# LEDDimmer.net
KiCad netlist of a schematic drawn in Altium Designer
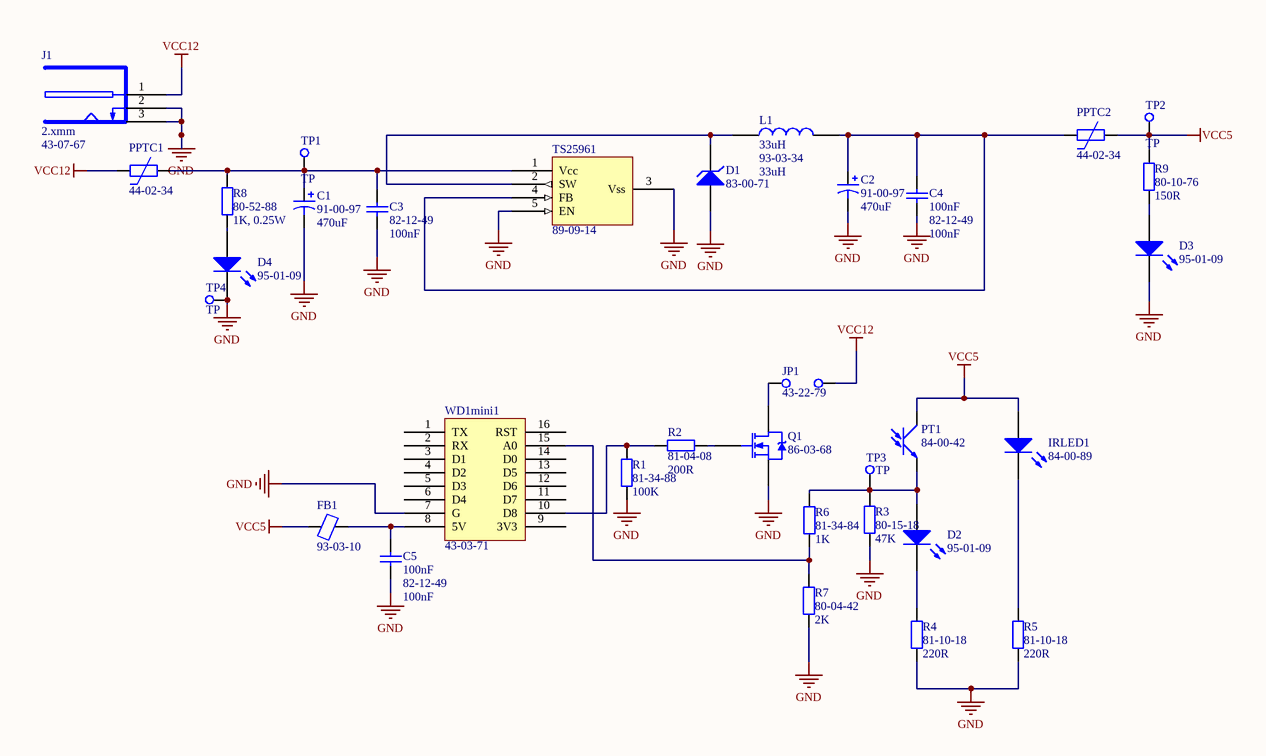
[diagram p0: LEDDimmer.SchDoc]

(export (version "E")
  (design (tool "Eeschema 10.0.6"))
  (components
    (comp (ref "C1")
      (value "470uF")
      (footprint "ELKO_CAP")
      (description "Polarized Capacitor")
      (fields (field (name "SUPPLIER") "91-00-97"))
      (libsource (lib "LEDDimmerLib") (part "CAP_ELECT"))
    )
    (comp (ref "C2")
      (value "470uF")
      (footprint "ELKO_CAP")
      (description "Polarized Capacitor")
      (fields (field (name "SUPPLIER") "91-00-97"))
      (libsource (lib "LEDDimmerLib") (part "CAP_ELECT"))
    )
    (comp (ref "C3")
      (value "100nF")
      (footprint "FP_0402_CAP_050")
      (description "Capacitor")
      (fields (field (name "SUPPLIER") "82-12-49"))
      (libsource (lib "LEDDimmerLib") (part "CAP_100n"))
    )
    (comp (ref "C4")
      (value "100nF")
      (footprint "FP_0402_CAP_050")
      (description "Capacitor")
      (fields (field (name "SUPPLIER") "82-12-49") (field (name "ALTIUM_VALUE") "100nF"))
      (libsource (lib "LEDDimmerLib") (part "CAP_100n"))
    )
    (comp (ref "C5")
      (value "100nF")
      (footprint "FP_0402_CAP_050")
      (description "Capacitor")
      (fields (field (name "SUPPLIER") "82-12-49") (field (name "ALTIUM_VALUE") "100nF"))
      (libsource (lib "LEDDimmerLib") (part "CAP_100n"))
    )
    (comp (ref "D1")
      (value "ZENER")
      (footprint "SCHOTTKY")
      (description "Zener Diode")
      (fields (field (name "SUPPLIER") "83-00-71"))
      (libsource (lib "LEDDimmerLib") (part "ZENER"))
    )
    (comp (ref "D2")
      (value "LED")
      (footprint "FP_0805_LED_GREEN")
      (description "Typical RED GaAs LED")
      (fields (field (name "SUPPLIER") "95-01-09"))
      (libsource (lib "LEDDimmerLib") (part "LED"))
    )
    (comp (ref "D3")
      (value "LED")
      (footprint "FP_0805_LED_RED")
      (description "Typical RED GaAs LED")
      (fields (field (name "SUPPLIER") "95-01-09"))
      (libsource (lib "LEDDimmerLib") (part "LED"))
    )
    (comp (ref "D4")
      (value "LED")
      (footprint "FP_0805_LED_RED")
      (description "Typical RED GaAs LED")
      (fields (field (name "SUPPLIER") "95-01-09"))
      (libsource (lib "LEDDimmerLib") (part "LED"))
    )
    (comp (ref "FB1")
      (value "FB")
      (footprint "FB")
      (description "Ferrite bead")
      (fields (field (name "SUPPLIER") "93-03-10"))
      (libsource (lib "LEDDimmerLib") (part "FB"))
    )
    (comp (ref "IRLED1")
      (value "IRLED")
      (footprint "IRLED")
      (description "InfraLED")
      (fields (field (name "SUPPLIER") "84-00-89"))
      (libsource (lib "LEDDimmerLib") (part "IRLED"))
    )
    (comp (ref "J1")
      (value "2.xmm")
      (footprint "FP_DC_TAP_ANYA")
      (description "2.xmm DC HEBA25 TÁPFESZÜLTSÉG ALJZAT ZÁRT, NYÁKBA 90°")
      (fields (field (name "SUPPLIER") "43-07-67"))
      (libsource (lib "LEDDimmerLib") (part "DC_TAP_ANYA"))
    )
    (comp (ref "JP1")
      (value "JUMPER")
      (footprint "CONN2")
      (description "Jumper Wire")
      (fields (field (name "SUPPLIER") "43-22-79"))
      (libsource (lib "LEDDimmerLib") (part "JUMPER"))
    )
    (comp (ref "L1")
      (value "33uH")
      (footprint "IND")
      (description "Inductor")
      (fields (field (name "SUPPLIER") "93-03-34") (field (name "ALTIUM_VALUE") "33uH"))
      (libsource (lib "LEDDimmerLib") (part "IND"))
    )
    (comp (ref "PPTC1")
      (value "PPTC")
      (footprint "PPTC")
      (description "Polymeric Positive Temperature Coefficient")
      (fields (field (name "SUPPLIER") "44-02-34"))
      (libsource (lib "LEDDimmerLib") (part "PPTC"))
    )
    (comp (ref "PPTC2")
      (value "PPTC")
      (footprint "PPTC")
      (description "Polymeric Positive Temperature Coefficient")
      (fields (field (name "SUPPLIER") "44-02-34"))
      (libsource (lib "LEDDimmerLib") (part "PPTC"))
    )
    (comp (ref "PT1")
      (value "PT")
      (footprint "IRLED")
      (description "Phototransistor")
      (fields (field (name "SUPPLIER") "84-00-42"))
      (libsource (lib "LEDDimmerLib") (part "PTRANS"))
    )
    (comp (ref "Q1")
      (value "NMOS")
      (footprint "IRL540N")
      (description "NXP - BSP030,115 - MOSFET, N CH, 30V, 10A, SOT223")
      (fields (field (name "SUPPLIER") "86-03-68"))
      (libsource (lib "LEDDimmerLib") (part "NMOS"))
    )
    (comp (ref "R1")
      (value "100K")
      (footprint "FP_0603_RES")
      (description "Resistor")
      (fields (field (name "SUPPLIER") "81-34-88"))
      (libsource (lib "LEDDimmerLib") (part "RES_100K"))
    )
    (comp (ref "R2")
      (value "200R")
      (footprint "FP_0603_RES")
      (description "Resistor")
      (fields (field (name "SUPPLIER") "81-04-08") (field (name "Comment") "200"))
      (libsource (lib "LEDDimmerLib") (part "RES_200R"))
    )
    (comp (ref "R3")
      (value "47K")
      (footprint "FP_0603_RES")
      (description "Resistor")
      (fields (field (name "SUPPLIER") "80-15-18"))
      (libsource (lib "LEDDimmerLib") (part "RES_47K"))
    )
    (comp (ref "R4")
      (value "220R")
      (footprint "FP_0603_RES")
      (description "Resistor")
      (fields (field (name "SUPPLIER") "81-10-18") (field (name "Comment") "220"))
      (libsource (lib "LEDDimmerLib") (part "RES_220R"))
    )
    (comp (ref "R5")
      (value "220R")
      (footprint "FP_0603_RES")
      (description "Resistor")
      (fields (field (name "SUPPLIER") "81-10-18") (field (name "Comment") "220"))
      (libsource (lib "LEDDimmerLib") (part "RES_220R"))
    )
    (comp (ref "R6")
      (value "1K")
      (footprint "FP_0603_RES")
      (description "Resistor")
      (fields (field (name "SUPPLIER") "81-34-84"))
      (libsource (lib "LEDDimmerLib") (part "RES_1K"))
    )
    (comp (ref "R7")
      (value "2K")
      (footprint "FP_0603_RES")
      (description "Resistor")
      (fields (field (name "SUPPLIER") "80-04-42"))
      (libsource (lib "LEDDimmerLib") (part "RES_2K"))
    )
    (comp (ref "R8")
      (value "1K, 0.25W")
      (footprint "FP_1206_RES")
      (description "Resistor")
      (fields (field (name "SUPPLIER") "80-52-88"))
      (libsource (lib "LEDDimmerLib") (part "RES_1K_025W"))
    )
    (comp (ref "R9")
      (value "150R")
      (footprint "FP_0805_RES")
      (description "Resistor")
      (fields (field (name "SUPPLIER") "80-10-76"))
      (libsource (lib "LEDDimmerLib") (part "RES_150R"))
    )
    (comp (ref "TP1")
      (value "TP")
      (footprint "FP_CONN1_TUSKE_254MM")
      (description "Test Point")
      (libsource (lib "LEDDimmerLib") (part "TP"))
    )
    (comp (ref "TP2")
      (value "TP")
      (footprint "FP_CONN1_TUSKE_254MM")
      (description "Test Point")
      (libsource (lib "LEDDimmerLib") (part "TP"))
    )
    (comp (ref "TP3")
      (value "TP")
      (footprint "FP_CONN1_TUSKE_254MM")
      (description "Test Point")
      (libsource (lib "LEDDimmerLib") (part "TP"))
    )
    (comp (ref "TP4")
      (value "TP")
      (footprint "FP_CONN1_TUSKE_254MM")
      (description "Test Point")
      (libsource (lib "LEDDimmerLib") (part "TP"))
    )
    (comp (ref "TS25961")
      (value "*")
      (footprint "TS2596")
      (description "TS2596 Buck DCDC")
      (fields (field (name "SUPPLIER") "89-09-14"))
      (libsource (lib "LEDDimmerLib") (part "TS2596"))
    )
    (comp (ref "WD1mini1")
      (value "WD1mini")
      (footprint "WEMOSD1")
      (description "Wemos D1 mini")
      (fields (field (name "SUPPLIER") "43-03-71"))
      (libsource (lib "LEDDimmerLib") (part "WEMOS"))
    )
  )
  (nets
    (net (code "1") (name "GND") (class "Default")
      (node (ref "C1") (pin "N") (pinfunction "N_N") (pintype "passive"))
      (node (ref "C2") (pin "N") (pinfunction "N_N") (pintype "passive"))
      (node (ref "C3") (pin "1") (pinfunction "1_1") (pintype "passive"))
      (node (ref "C4") (pin "1") (pinfunction "1_1") (pintype "passive"))
      (node (ref "C5") (pin "1") (pinfunction "1_1") (pintype "passive"))
      (node (ref "D1") (pin "1") (pinfunction "A_1") (pintype "passive"))
      (node (ref "D3") (pin "2") (pinfunction "K_2") (pintype "passive"))
      (node (ref "D4") (pin "2") (pinfunction "K_2") (pintype "passive"))
      (node (ref "J1") (pin "2") (pinfunction "GND_2") (pintype "power_in"))
      (node (ref "J1") (pin "3") (pinfunction "GND_3") (pintype "power_in"))
      (node (ref "Q1") (pin "3") (pinfunction "S_3") (pintype "passive"))
      (node (ref "R1") (pin "1") (pinfunction "1_1") (pintype "passive"))
      (node (ref "R3") (pin "1") (pinfunction "1_1") (pintype "passive"))
      (node (ref "R4") (pin "1") (pinfunction "1_1") (pintype "passive"))
      (node (ref "R5") (pin "1") (pinfunction "1_1") (pintype "passive"))
      (node (ref "R7") (pin "1") (pinfunction "1_1") (pintype "passive"))
      (node (ref "TP4") (pin "1") (pinfunction "C1_1") (pintype "passive"))
      (node (ref "TS25961") (pin "3") (pinfunction "Vss_3") (pintype "power_in"))
      (node (ref "TS25961") (pin "5") (pinfunction "EN_5") (pintype "input"))
      (node (ref "WD1mini1") (pin "7") (pinfunction "G_7") (pintype "passive"))
    )
    (net (code "2") (name "Net-(D1-K)") (class "Default")
      (node (ref "D1") (pin "2") (pinfunction "K_2") (pintype "passive"))
      (node (ref "L1") (pin "1") (pinfunction "1_1") (pintype "passive"))
      (node (ref "TS25961") (pin "2") (pinfunction "SW_2") (pintype "output"))
    )
    (net (code "3") (name "Net-(D2-A)") (class "Default")
      (node (ref "D2") (pin "1") (pinfunction "A_1") (pintype "passive"))
      (node (ref "PT1") (pin "2") (pinfunction "K_2") (pintype "passive"))
      (node (ref "R3") (pin "2") (pinfunction "2_2") (pintype "passive"))
      (node (ref "R6") (pin "2") (pinfunction "2_2") (pintype "passive"))
      (node (ref "TP3") (pin "1") (pinfunction "C1_1") (pintype "passive"))
    )
    (net (code "4") (name "Net-(D2-K)") (class "Default")
      (node (ref "D2") (pin "2") (pinfunction "K_2") (pintype "passive"))
      (node (ref "R4") (pin "2") (pinfunction "2_2") (pintype "passive"))
    )
    (net (code "5") (name "Net-(D3-A)") (class "Default")
      (node (ref "D3") (pin "1") (pinfunction "A_1") (pintype "passive"))
      (node (ref "R9") (pin "1") (pinfunction "1_1") (pintype "passive"))
    )
    (net (code "6") (name "Net-(D4-A)") (class "Default")
      (node (ref "D4") (pin "1") (pinfunction "A_1") (pintype "passive"))
      (node (ref "R8") (pin "1") (pinfunction "1_1") (pintype "passive"))
    )
    (net (code "7") (name "Net-(IRLED1-K)") (class "Default")
      (node (ref "IRLED1") (pin "2") (pinfunction "K_2") (pintype "passive"))
      (node (ref "R5") (pin "2") (pinfunction "2_2") (pintype "passive"))
    )
    (net (code "8") (name "Net-(JP1-C2)") (class "Default")
      (node (ref "JP1") (pin "2") (pinfunction "C2_2") (pintype "passive"))
      (node (ref "Q1") (pin "2") (pinfunction "D_2") (pintype "passive"))
    )
    (net (code "9") (name "Net-(Q1-G)") (class "Default")
      (node (ref "Q1") (pin "1") (pinfunction "G_1") (pintype "passive"))
      (node (ref "R2") (pin "2") (pinfunction "2_2") (pintype "passive"))
    )
    (net (code "10") (name "Net-(TP1-C1)") (class "Default")
      (node (ref "C1") (pin "P") (pinfunction "P_P") (pintype "passive"))
      (node (ref "C3") (pin "2") (pinfunction "2_2") (pintype "passive"))
      (node (ref "PPTC1") (pin "2") (pinfunction "2_2") (pintype "passive"))
      (node (ref "R8") (pin "2") (pinfunction "2_2") (pintype "passive"))
      (node (ref "TP1") (pin "1") (pinfunction "C1_1") (pintype "passive"))
      (node (ref "TS25961") (pin "1") (pinfunction "Vcc_1") (pintype "power_in"))
    )
    (net (code "11") (name "Net-(TS25961-FB)") (class "Default")
      (node (ref "C2") (pin "P") (pinfunction "P_P") (pintype "passive"))
      (node (ref "C4") (pin "2") (pinfunction "2_2") (pintype "passive"))
      (node (ref "L1") (pin "2") (pinfunction "2_2") (pintype "passive"))
      (node (ref "PPTC2") (pin "1") (pinfunction "1_1") (pintype "passive"))
      (node (ref "TS25961") (pin "4") (pinfunction "FB_4") (pintype "input"))
    )
    (net (code "12") (name "Net-(WD1mini1-5V)") (class "Default")
      (node (ref "C5") (pin "2") (pinfunction "2_2") (pintype "passive"))
      (node (ref "FB1") (pin "2") (pinfunction "2_2") (pintype "passive"))
      (node (ref "WD1mini1") (pin "8") (pinfunction "5V_8") (pintype "passive"))
    )
    (net (code "13") (name "Net-(WD1mini1-A0)") (class "Default")
      (node (ref "R6") (pin "1") (pinfunction "1_1") (pintype "passive"))
      (node (ref "R7") (pin "2") (pinfunction "2_2") (pintype "passive"))
      (node (ref "WD1mini1") (pin "15") (pinfunction "A0_15") (pintype "passive"))
    )
    (net (code "14") (name "Net-(WD1mini1-D8)") (class "Default")
      (node (ref "R1") (pin "2") (pinfunction "2_2") (pintype "passive"))
      (node (ref "R2") (pin "1") (pinfunction "1_1") (pintype "passive"))
      (node (ref "WD1mini1") (pin "10") (pinfunction "D8_10") (pintype "passive"))
    )
    (net (code "15") (name "VCC5") (class "Default")
      (node (ref "FB1") (pin "1") (pinfunction "1_1") (pintype "passive"))
      (node (ref "IRLED1") (pin "1") (pinfunction "A_1") (pintype "passive"))
      (node (ref "PPTC2") (pin "2") (pinfunction "2_2") (pintype "passive"))
      (node (ref "PT1") (pin "1") (pinfunction "A_1") (pintype "passive"))
      (node (ref "R9") (pin "2") (pinfunction "2_2") (pintype "passive"))
      (node (ref "TP2") (pin "1") (pinfunction "C1_1") (pintype "passive"))
    )
    (net (code "16") (name "VCC12") (class "Default")
      (node (ref "J1") (pin "1") (pinfunction "9V_1") (pintype "power_in"))
      (node (ref "JP1") (pin "1") (pinfunction "C1_1") (pintype "passive"))
      (node (ref "PPTC1") (pin "1") (pinfunction "1_1") (pintype "passive"))
    )
    (net (code "17") (name "unconnected-(WD1mini1-3V3-Pad9)") (class "Default")
      (node (ref "WD1mini1") (pin "9") (pinfunction "3V3_9") (pintype "passive"))
    )
    (net (code "18") (name "unconnected-(WD1mini1-D0-Pad14)") (class "Default")
      (node (ref "WD1mini1") (pin "14") (pinfunction "D0_14") (pintype "passive"))
    )
    (net (code "19") (name "unconnected-(WD1mini1-D1-Pad3)") (class "Default")
      (node (ref "WD1mini1") (pin "3") (pinfunction "D1_3") (pintype "passive"))
    )
    (net (code "20") (name "unconnected-(WD1mini1-D2-Pad4)") (class "Default")
      (node (ref "WD1mini1") (pin "4") (pinfunction "D2_4") (pintype "passive"))
    )
    (net (code "21") (name "unconnected-(WD1mini1-D3-Pad5)") (class "Default")
      (node (ref "WD1mini1") (pin "5") (pinfunction "D3_5") (pintype "passive"))
    )
    (net (code "22") (name "unconnected-(WD1mini1-D4-Pad6)") (class "Default")
      (node (ref "WD1mini1") (pin "6") (pinfunction "D4_6") (pintype "passive"))
    )
    (net (code "23") (name "unconnected-(WD1mini1-D5-Pad13)") (class "Default")
      (node (ref "WD1mini1") (pin "13") (pinfunction "D5_13") (pintype "passive"))
    )
    (net (code "24") (name "unconnected-(WD1mini1-D6-Pad12)") (class "Default")
      (node (ref "WD1mini1") (pin "12") (pinfunction "D6_12") (pintype "passive"))
    )
    (net (code "25") (name "unconnected-(WD1mini1-D7-Pad11)") (class "Default")
      (node (ref "WD1mini1") (pin "11") (pinfunction "D7_11") (pintype "passive"))
    )
    (net (code "26") (name "unconnected-(WD1mini1-RST-Pad16)") (class "Default")
      (node (ref "WD1mini1") (pin "16") (pinfunction "RST_16") (pintype "passive"))
    )
    (net (code "27") (name "unconnected-(WD1mini1-RX-Pad2)") (class "Default")
      (node (ref "WD1mini1") (pin "2") (pinfunction "RX_2") (pintype "passive"))
    )
    (net (code "28") (name "unconnected-(WD1mini1-TX-Pad1)") (class "Default")
      (node (ref "WD1mini1") (pin "1") (pinfunction "TX_1") (pintype "passive"))
    )
  )
)
